# RTx_Charger.net
KiCad netlist of a schematic drawn in EAGLE
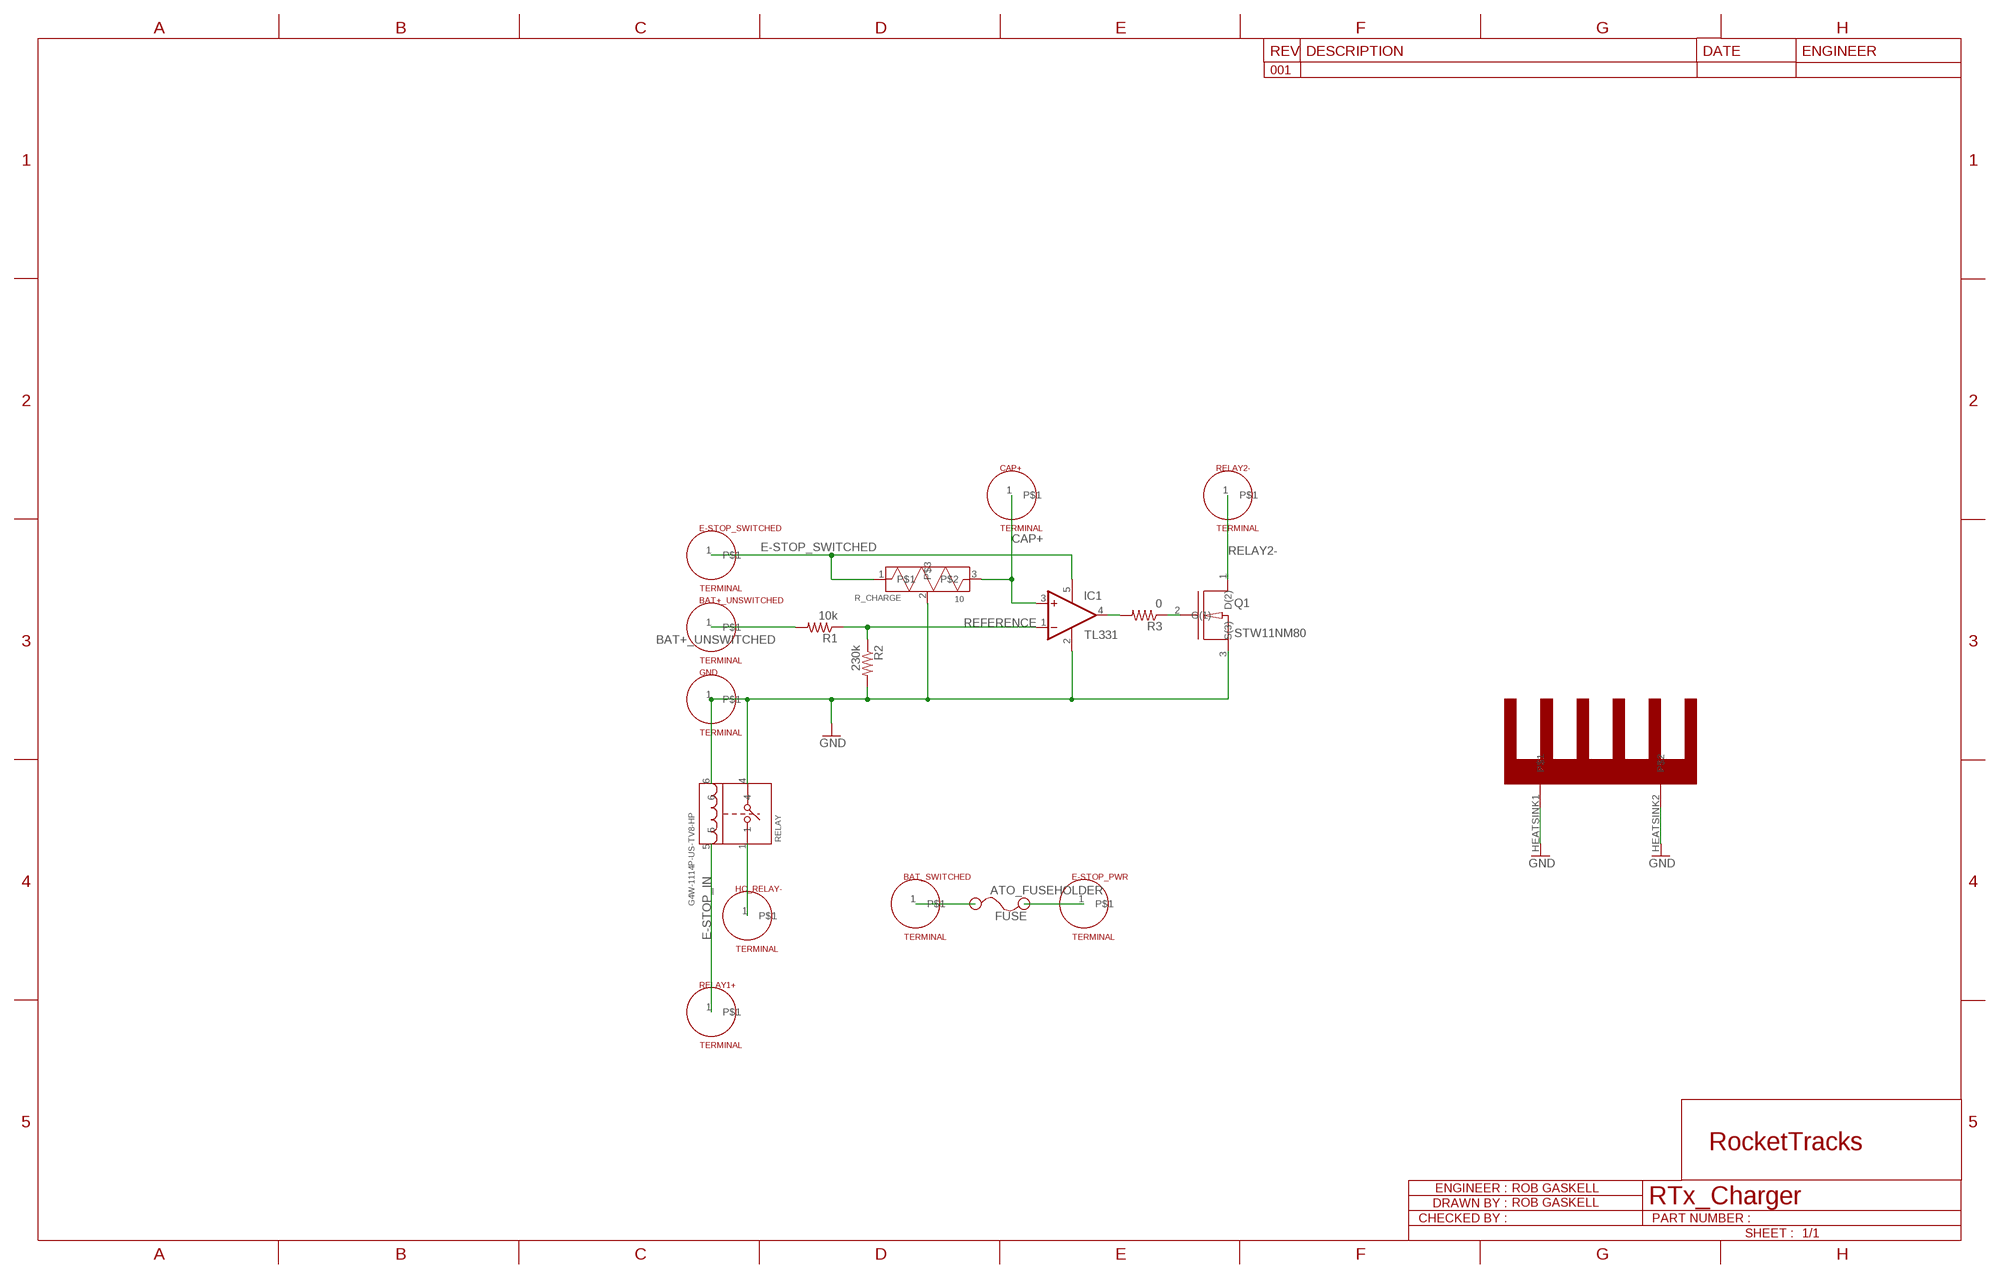
[diagram p0: schematic, sheet 1]

(export (version "E")
  (design (tool "Eeschema 10.0.6"))
  (components
    (comp (ref "BAT+_UNSWITCHED")
      (value "TERMINAL")
      (footprint "eagle-import:TERMINAL_STUD")
      (libsource (lib "eagle-import") (part "TERMINALSTUD"))
    )
    (comp (ref "BAT_SWITCHED")
      (value "TERMINAL")
      (footprint "eagle-import:TERMINAL_NO-STUD")
      (libsource (lib "eagle-import") (part "TERMINALNO_STUD"))
    )
    (comp (ref "CAP+")
      (value "TERMINAL")
      (footprint "eagle-import:TERMINAL_STUD")
      (libsource (lib "eagle-import") (part "TERMINALSTUD"))
    )
    (comp (ref "E-STOP_PWR")
      (value "TERMINAL")
      (footprint "eagle-import:TERMINAL_STUD")
      (libsource (lib "eagle-import") (part "TERMINALSTUD"))
    )
    (comp (ref "E-STOP_SWITCHED")
      (value "TERMINAL")
      (footprint "eagle-import:TERMINAL_NO-STUD")
      (libsource (lib "eagle-import") (part "TERMINALNO_STUD"))
    )
    (comp (ref "FUSE")
      (value "ATO_FUSEHOLDER")
      (footprint "eagle-import:ATO_BLADE_FUSE")
      (libsource (lib "eagle-import") (part "FUSEATO_FUSEHOLDER"))
    )
    (comp (ref "GND")
      (value "TERMINAL")
      (footprint "eagle-import:TERMINAL_STUD")
      (libsource (lib "eagle-import") (part "TERMINALSTUD"))
    )
    (comp (ref "HC_RELAY-")
      (value "TERMINAL")
      (footprint "eagle-import:TERMINAL_NO-STUD")
      (libsource (lib "eagle-import") (part "TERMINALNO_STUD"))
    )
    (comp (ref "HEATSINK")
      (value "WA-T247-101E")
      (footprint "eagle-import:WA-T247-101E")
      (libsource (lib "eagle-import") (part "WA-T247-101E"))
    )
    (comp (ref "IC1")
      (value "TL331")
      (footprint "eagle-import:DBV-R-PDSO-G5")
      (libsource (lib "eagle-import") (part "TL331"))
    )
    (comp (ref "Q1")
      (value "STW11NM80")
      (footprint "eagle-import:TO-247")
      (libsource (lib "eagle-import") (part "STW11NM80"))
    )
    (comp (ref "R1")
      (value "10k")
      (footprint "eagle-import:R1206")
      (libsource (lib "eagle-import") (part "R-US_R1206"))
    )
    (comp (ref "R2")
      (value "230k")
      (footprint "eagle-import:R1206")
      (libsource (lib "eagle-import") (part "R-US_R1206"))
    )
    (comp (ref "R3")
      (value "0")
      (footprint "eagle-import:R1206")
      (libsource (lib "eagle-import") (part "R-US_R1206"))
    )
    (comp (ref "RELAY")
      (value "G4W-1114P-US-TV8-HP")
      (footprint "eagle-import:G4W-1114P-US-TV8-HP")
      (libsource (lib "eagle-import") (part "G4W-1114P-US-TV8-HP"))
    )
    (comp (ref "RELAY1+")
      (value "TERMINAL")
      (footprint "eagle-import:TERMINAL_NO-STUD")
      (libsource (lib "eagle-import") (part "TERMINALNO_STUD"))
    )
    (comp (ref "RELAY2-")
      (value "TERMINAL")
      (footprint "eagle-import:TERMINAL_NO-STUD")
      (libsource (lib "eagle-import") (part "TERMINALNO_STUD"))
    )
    (comp (ref "R_CHARGE")
      (value "10")
      (footprint "eagle-import:TEH70")
      (libsource (lib "eagle-import") (part "TEH70"))
    )
  )
  (nets
    (net (code "1") (name "/BAT+_UNSWITCHED") (class "Default")
      (node (ref "BAT+_UNSWITCHED") (pin "1") (pinfunction "P$1_1") (pintype "bidirectional"))
      (node (ref "R1") (pin "2") (pinfunction "2_2") (pintype "passive"))
    )
    (net (code "2") (name "/CAP+") (class "Default")
      (node (ref "CAP+") (pin "1") (pinfunction "P$1_1") (pintype "bidirectional"))
      (node (ref "IC1") (pin "3") (pinfunction "+IN_3") (pintype "input"))
      (node (ref "R_CHARGE") (pin "3") (pinfunction "P$2_3") (pintype "bidirectional"))
    )
    (net (code "3") (name "/E-STOP_IN") (class "Default")
      (node (ref "RELAY") (pin "5") (pinfunction "5_5") (pintype "power_in"))
      (node (ref "RELAY1+") (pin "1") (pinfunction "P$1_1") (pintype "bidirectional"))
    )
    (net (code "4") (name "/E-STOP_SWITCHED") (class "Default")
      (node (ref "E-STOP_SWITCHED") (pin "1") (pinfunction "P$1_1") (pintype "bidirectional"))
      (node (ref "IC1") (pin "5") (pinfunction "V+_5") (pintype "power_in"))
      (node (ref "R_CHARGE") (pin "1") (pinfunction "P$1_1") (pintype "bidirectional"))
    )
    (net (code "5") (name "/REFERENCE") (class "Default")
      (node (ref "IC1") (pin "1") (pinfunction "-IN_1") (pintype "input"))
      (node (ref "R1") (pin "1") (pinfunction "1_1") (pintype "passive"))
      (node (ref "R2") (pin "1") (pinfunction "1_1") (pintype "passive"))
    )
    (net (code "6") (name "/RELAY2-") (class "Default")
      (node (ref "Q1") (pin "1") (pinfunction "D(2)_1") (pintype "bidirectional"))
      (node (ref "RELAY2-") (pin "1") (pinfunction "P$1_1") (pintype "bidirectional"))
    )
    (net (code "7") (name "GND") (class "Default")
      (node (ref "GND") (pin "1") (pinfunction "P$1_1") (pintype "bidirectional"))
      (node (ref "HEATSINK") (pin "HEATSINK1") (pinfunction "P$1_HEATSINK1") (pintype "bidirectional"))
      (node (ref "HEATSINK") (pin "HEATSINK2") (pinfunction "P$2_HEATSINK2") (pintype "bidirectional"))
      (node (ref "IC1") (pin "2") (pinfunction "GND_2") (pintype "power_in"))
      (node (ref "Q1") (pin "3") (pinfunction "S(3)_3") (pintype "bidirectional"))
      (node (ref "R2") (pin "2") (pinfunction "2_2") (pintype "passive"))
      (node (ref "RELAY") (pin "4") (pinfunction "4_4") (pintype "bidirectional"))
      (node (ref "RELAY") (pin "6") (pinfunction "6_6") (pintype "power_in"))
      (node (ref "R_CHARGE") (pin "2") (pinfunction "P$3_2") (pintype "power_in"))
    )
    (net (code "8") (name "Net-(BAT_SWITCHED-P$1)") (class "Default")
      (node (ref "BAT_SWITCHED") (pin "1") (pinfunction "P$1_1") (pintype "bidirectional"))
      (node (ref "FUSE") (pin "2.1") (pinfunction "C_2.1") (pintype "passive"))
      (node (ref "FUSE") (pin "2.2") (pinfunction "C_2.2") (pintype "passive"))
      (node (ref "FUSE") (pin "2.3") (pinfunction "C_2.3") (pintype "passive"))
      (node (ref "FUSE") (pin "2.4") (pinfunction "C_2.4") (pintype "passive"))
    )
    (net (code "9") (name "Net-(E-STOP_PWR-P$1)") (class "Default")
      (node (ref "E-STOP_PWR") (pin "1") (pinfunction "P$1_1") (pintype "bidirectional"))
      (node (ref "FUSE") (pin "1.1") (pinfunction "A_1.1") (pintype "passive"))
      (node (ref "FUSE") (pin "1.2") (pinfunction "A_1.2") (pintype "passive"))
      (node (ref "FUSE") (pin "1.3") (pinfunction "A_1.3") (pintype "passive"))
      (node (ref "FUSE") (pin "1.4") (pinfunction "A_1.4") (pintype "passive"))
    )
    (net (code "10") (name "Net-(HC_RELAY--P$1)") (class "Default")
      (node (ref "HC_RELAY-") (pin "1") (pinfunction "P$1_1") (pintype "bidirectional"))
      (node (ref "RELAY") (pin "1") (pinfunction "1_1") (pintype "bidirectional"))
    )
    (net (code "11") (name "Net-(IC1-OUT)") (class "Default")
      (node (ref "IC1") (pin "4") (pinfunction "OUT_4") (pintype "output"))
      (node (ref "R3") (pin "2") (pinfunction "2_2") (pintype "passive"))
    )
    (net (code "12") (name "Net-(Q1-G(1))") (class "Default")
      (node (ref "Q1") (pin "2") (pinfunction "G(1)_2") (pintype "bidirectional"))
      (node (ref "R3") (pin "1") (pinfunction "1_1") (pintype "passive"))
    )
  )
)
